# Sheet1.net
KiCad netlist of a schematic drawn in Altium Designer
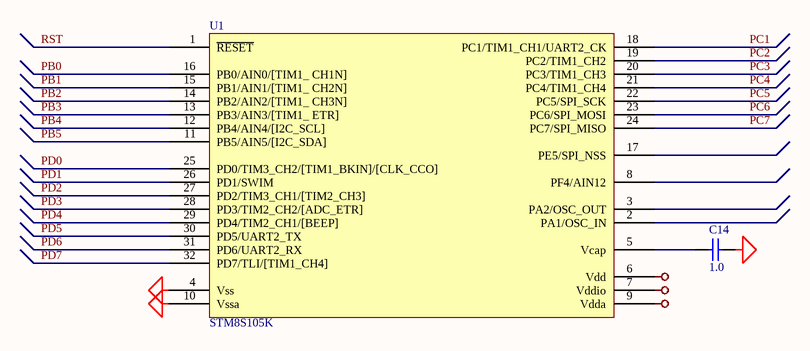
[diagram p0: Sheet1.SchDoc]

(export (version "E")
  (design (tool "Eeschema 10.0.6"))
  (components
    (comp (ref "C14")
      (value "1.0")
      (footprint "_1206")
      (description "Capacitor")
      (fields (field (name "MANUFACTURER") "Generic Components") (field (name "PUBLISHER") "Altium Limited"))
      (libsource (lib "Miscellaneous Devices") (part "Cap Semi"))
    )
    (comp (ref "U1")
      (value "STM8S105K")
      (footprint "QFP7X7-G32/X.5N")
      (libsource (lib "PAL") (part "STM8S105K"))
    )
  )
  (nets
    (net (code "1") (name "+5v") (class "Default")
      (node (ref "U1") (pin "6") (pinfunction "Vdd_6") (pintype "passive"))
      (node (ref "U1") (pin "7") (pinfunction "Vddio_7") (pintype "passive"))
      (node (ref "U1") (pin "9") (pinfunction "Vdda_9") (pintype "passive"))
    )
    (net (code "2") (name "/PB0") (class "Default")
      (node (ref "U1") (pin "16") (pinfunction "PB0/AIN0/[TIM1__CH1N]_16") (pintype "passive"))
    )
    (net (code "3") (name "/PB1") (class "Default")
      (node (ref "U1") (pin "15") (pinfunction "PB1/AIN1/[TIM1__CH2N]_15") (pintype "passive"))
    )
    (net (code "4") (name "/PB2") (class "Default")
      (node (ref "U1") (pin "14") (pinfunction "PB2/AIN2/[TIM1__CH3N]_14") (pintype "passive"))
    )
    (net (code "5") (name "/PB3") (class "Default")
      (node (ref "U1") (pin "13") (pinfunction "PB3/AIN3/[TIM1__ETR]_13") (pintype "passive"))
    )
    (net (code "6") (name "/PB4") (class "Default")
      (node (ref "U1") (pin "12") (pinfunction "PB4/AIN4/[I2C_SCL]_12") (pintype "passive"))
    )
    (net (code "7") (name "/PB5") (class "Default")
      (node (ref "U1") (pin "11") (pinfunction "PB5/AIN5/[I2C_SDA]_11") (pintype "passive"))
    )
    (net (code "8") (name "/PC1") (class "Default")
      (node (ref "U1") (pin "18") (pinfunction "PC1/TIM1_CH1/UART2_CK_18") (pintype "passive"))
    )
    (net (code "9") (name "/PC2") (class "Default")
      (node (ref "U1") (pin "19") (pinfunction "PC2/TIM1_CH2_19") (pintype "passive"))
    )
    (net (code "10") (name "/PC3") (class "Default")
      (node (ref "U1") (pin "20") (pinfunction "PC3/TIM1_CH3_20") (pintype "passive"))
    )
    (net (code "11") (name "/PC4") (class "Default")
      (node (ref "U1") (pin "21") (pinfunction "PC4/TIM1_CH4_21") (pintype "passive"))
    )
    (net (code "12") (name "/PC5") (class "Default")
      (node (ref "U1") (pin "22") (pinfunction "PC5/SPI_SCK_22") (pintype "passive"))
    )
    (net (code "13") (name "/PC6") (class "Default")
      (node (ref "U1") (pin "23") (pinfunction "PC6/SPI_MOSI_23") (pintype "passive"))
    )
    (net (code "14") (name "/PC7") (class "Default")
      (node (ref "U1") (pin "24") (pinfunction "PC7/SPI_MISO_24") (pintype "passive"))
    )
    (net (code "15") (name "/PD0") (class "Default")
      (node (ref "U1") (pin "25") (pinfunction "PD0/TIM3_CH2/[TIM1_BKIN]/[CLK_CCO]_25") (pintype "passive"))
    )
    (net (code "16") (name "/PD1") (class "Default")
      (node (ref "U1") (pin "26") (pinfunction "PD1/SWIM_26") (pintype "passive"))
    )
    (net (code "17") (name "/PD2") (class "Default")
      (node (ref "U1") (pin "27") (pinfunction "PD2/TIM3_CH1/[TIM2_CH3]_27") (pintype "passive"))
    )
    (net (code "18") (name "/PD3") (class "Default")
      (node (ref "U1") (pin "28") (pinfunction "PD3/TIM2_CH2/[ADC_ETR]_28") (pintype "passive"))
    )
    (net (code "19") (name "/PD4") (class "Default")
      (node (ref "U1") (pin "29") (pinfunction "PD4/TIM2_CH1/[BEEP]_29") (pintype "passive"))
    )
    (net (code "20") (name "/PD5") (class "Default")
      (node (ref "U1") (pin "30") (pinfunction "PD5/UART2_TX_30") (pintype "passive"))
    )
    (net (code "21") (name "/PD6") (class "Default")
      (node (ref "U1") (pin "31") (pinfunction "PD6/UART2_RX_31") (pintype "passive"))
    )
    (net (code "22") (name "/PD7") (class "Default")
      (node (ref "U1") (pin "32") (pinfunction "PD7/TLI/[TIM1_CH4]_32") (pintype "passive"))
    )
    (net (code "23") (name "/RST") (class "Default")
      (node (ref "U1") (pin "1") (pinfunction "~{RESET}_1") (pintype "passive"))
    )
    (net (code "24") (name "GND") (class "Default")
      (node (ref "C14") (pin "1") (pinfunction "1_1") (pintype "passive"))
      (node (ref "U1") (pin "10") (pinfunction "Vssa_10") (pintype "passive"))
      (node (ref "U1") (pin "4") (pinfunction "Vss_4") (pintype "passive"))
    )
    (net (code "25") (name "Net-(U1-Vcap)") (class "Default")
      (node (ref "C14") (pin "2") (pinfunction "2_2") (pintype "passive"))
      (node (ref "U1") (pin "5") (pinfunction "Vcap_5") (pintype "passive"))
    )
    (net (code "26") (name "unconnected-(U1-PA1{slash}OSC_IN-Pad2)") (class "Default")
      (node (ref "U1") (pin "2") (pinfunction "PA1/OSC_IN_2") (pintype "passive"))
    )
    (net (code "27") (name "unconnected-(U1-PA2{slash}OSC_OUT-Pad3)") (class "Default")
      (node (ref "U1") (pin "3") (pinfunction "PA2/OSC_OUT_3") (pintype "passive"))
    )
    (net (code "28") (name "unconnected-(U1-PE5{slash}SPI_NSS-Pad17)") (class "Default")
      (node (ref "U1") (pin "17") (pinfunction "PE5/SPI_NSS_17") (pintype "passive"))
    )
    (net (code "29") (name "unconnected-(U1-PF4{slash}AIN12-Pad8)") (class "Default")
      (node (ref "U1") (pin "8") (pinfunction "PF4/AIN12_8") (pintype "passive"))
    )
  )
)
